# RF_Filter.net
KiCad netlist of a schematic drawn in Altium Designer
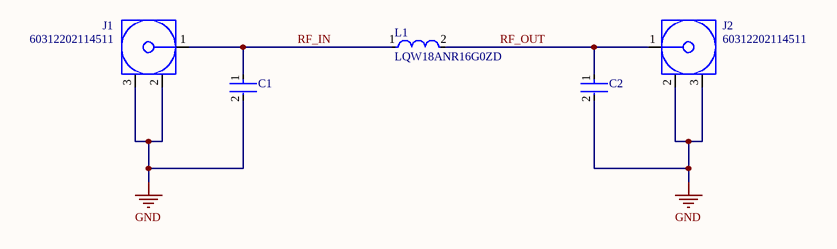
[diagram p0: RF_Filter.SchDoc]

(export (version "E")
  (design (tool "Eeschema 10.0.6"))
  (components
    (comp (ref "C1")
      (value "CC0603JRNPO9BN330")
      (footprint "FP-CC0603-0_9-IPC_C")
      (description "CAP CER 33PF 50V C0G/NPO 0603")
      (fields (field (name "TOLERANCE") "5%") (field (name "VOLTAGE") "50V"))
      (libsource (lib "Altium Content Vault") (part "b4654b650e69147ec39a6b967a45e02"))
    )
    (comp (ref "C2")
      (value "CC0603JRNPO9BN330")
      (footprint "FP-CC0603-0_9-IPC_C")
      (description "CAP CER 33PF 50V C0G/NPO 0603")
      (fields (field (name "TOLERANCE") "5%") (field (name "VOLTAGE") "50V"))
      (libsource (lib "Altium Content Vault") (part "b4654b650e69147ec39a6b967a45e02"))
    )
    (comp (ref "J1")
      (value "60312202114511")
      (footprint "60312202114511")
      (description "Rf Coax Conn, Sma Jack, 50 Ohm, Pcb Rohs Compliant: Yes")
      (libsource (lib "Altium Content Vault") (part "Jack_2GND"))
    )
    (comp (ref "J2")
      (value "60312202114511")
      (footprint "60312202114511")
      (description "Rf Coax Conn, Sma Jack, 50 Ohm, Pcb Rohs Compliant: Yes")
      (libsource (lib "Altium Content Vault") (part "Jack_2GND"))
    )
    (comp (ref "L1")
      (value "LQW18ANR16G0ZD")
      (footprint "FP-LQW18AN_00-MFG")
      (description "Wire Wound RF Inductor for Automotive 160nH ±2% 150mA 2.1Ω 0603 (1608)")
      (libsource (lib "Altium Content Vault") (part "725321dda6339637d4d059423bc1c3c"))
    )
  )
  (nets
    (net (code "1") (name "/RF_IN") (class "Default")
      (node (ref "C1") (pin "1") (pinfunction "1_1") (pintype "passive"))
      (node (ref "J1") (pin "1") (pinfunction "Signal_1") (pintype "passive"))
      (node (ref "L1") (pin "1") (pinfunction "1_1") (pintype "passive"))
    )
    (net (code "2") (name "/RF_OUT") (class "Default")
      (node (ref "C2") (pin "1") (pinfunction "1_1") (pintype "passive"))
      (node (ref "J2") (pin "1") (pinfunction "Signal_1") (pintype "passive"))
      (node (ref "L1") (pin "2") (pinfunction "2_2") (pintype "passive"))
    )
    (net (code "3") (name "GND") (class "Default")
      (node (ref "C1") (pin "2") (pinfunction "2_2") (pintype "passive"))
      (node (ref "C2") (pin "2") (pinfunction "2_2") (pintype "passive"))
      (node (ref "J1") (pin "2") (pinfunction "GND_2") (pintype "passive"))
      (node (ref "J1") (pin "3") (pinfunction "GND_3") (pintype "passive"))
      (node (ref "J2") (pin "2") (pinfunction "GND_2") (pintype "passive"))
      (node (ref "J2") (pin "3") (pinfunction "GND_3") (pintype "passive"))
    )
  )
)
